# REGENIX_USB-C.net
KiCad netlist of a schematic drawn in Altium Designer
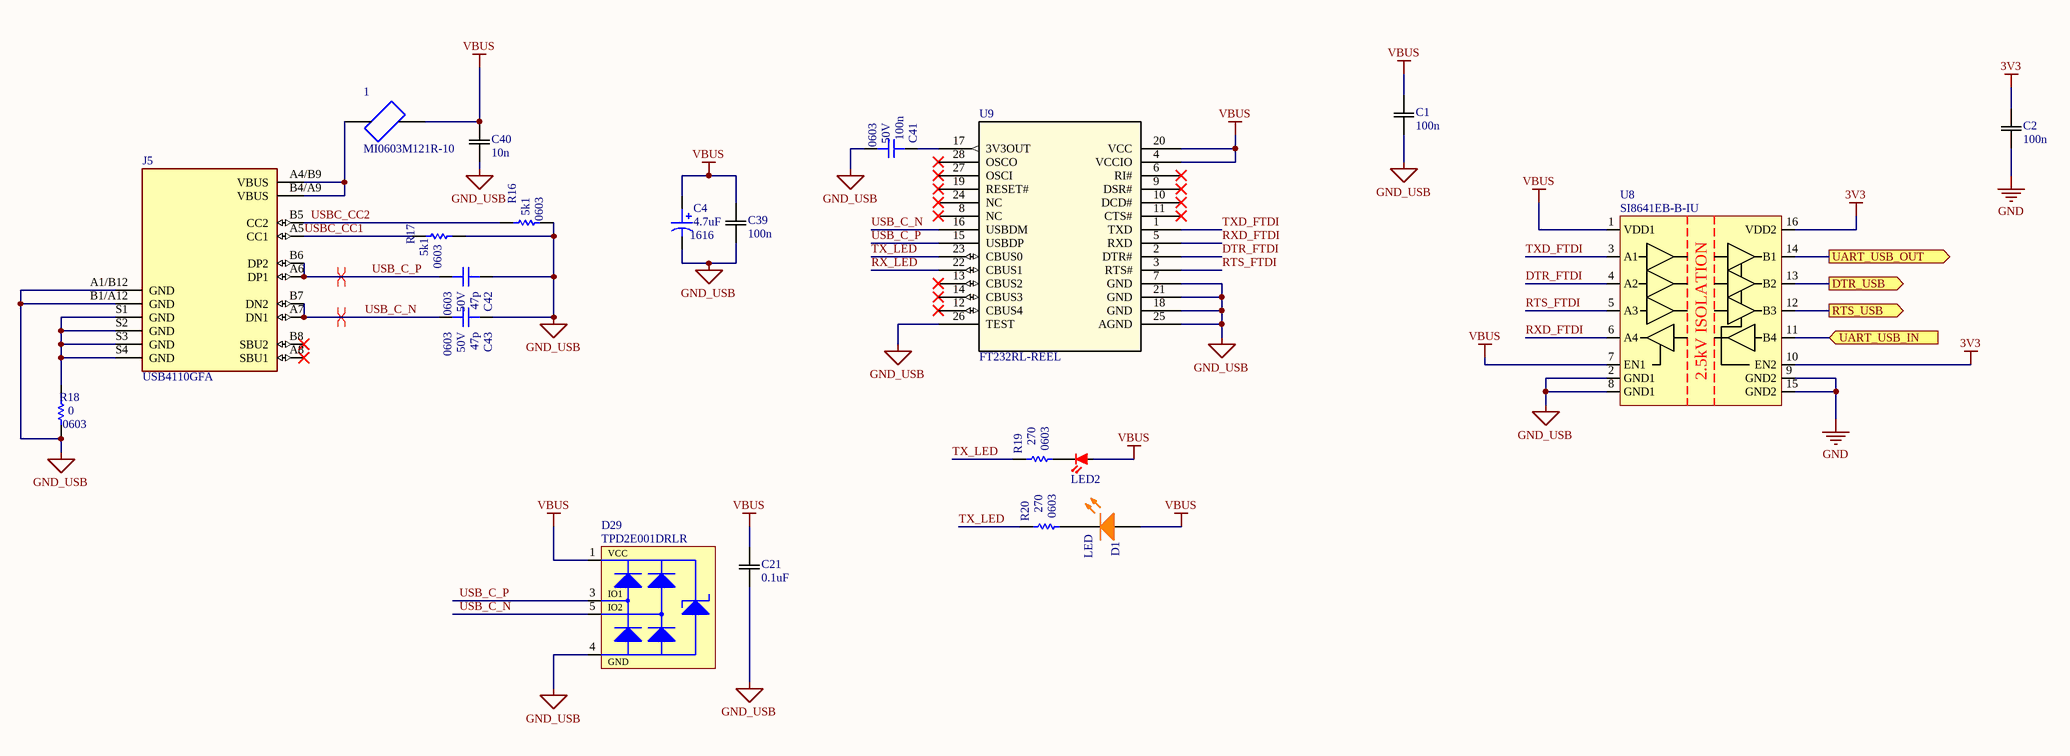
[diagram p0: REGENIX_USB-C.SchDoc]

(export (version "E")
  (design (tool "Eeschema 10.0.6"))
  (components
    (comp (ref "1")
      (value "MI0603M121R-10")
      (footprint "FB_MI0603M121R-10")
      (description "Ferrite Bead (Chip Bead), 1.6 x 0.8 x 0.8mm (0603), 120Ohms impedance at 25 MHz")
      (fields (field (name "MF") "Laird"))
      (libsource (lib "MI0603M121R-10") (part "MI0603M121R-10"))
    )
    (comp (ref "C1")
      (value "100n")
      (footprint "CAP_CL10_SAM")
      (description "CAP CER 0.1UF 50V X7R 0603 CL10B104KB8NNWC")
      (libsource (lib "CL10B104KB8NNWC") (part "CL10B104KB8NNWC"))
    )
    (comp (ref "C2")
      (value "100n")
      (footprint "CAP_CL10_SAM")
      (description "CAP CER 0.1UF 50V X7R 0603 CL10B104KB8NNWC")
      (libsource (lib "CL10B104KB8NNWC") (part "CL10B104KB8NNWC"))
    )
    (comp (ref "C4")
      (value "4.7uF")
      (footprint "CAP_ALU_1616_vishay")
      (description "CAP - ALU 470uF 20% 50V - 1616")
      (fields
        (field (name "MFG") "Vishay Dale")
        (field (name "MFG PART NUMBER") "MAL214699108E3")
        (field (name "PACKAGE") "1616")
        (field (name "CREATEDBY") "Jonathan Bouchard")
      )
      (libsource (lib "S7CAS_LIB2023") (part "CAP_ALU_MAL214699108E3"))
    )
    (comp (ref "C21")
      (value "0.1uF")
      (footprint "CAP_CL10_SAM")
      (description "CAP CER 0.1UF 50V X7R 0603 CL10B104KB8NNWC")
      (libsource (lib "CL10B104KB8NNWC") (part "CL10B104KB8NNWC"))
    )
    (comp (ref "C39")
      (value "100n")
      (footprint "CAP_CL10_SAM")
      (description "CAP CER 0.1UF 50V X7R 0603 CL10B104KB8NNWC")
      (libsource (lib "CL10B104KB8NNWC") (part "CL10B104KB8NNWC"))
    )
    (comp (ref "C40")
      (value "10n")
      (footprint "CAP_CL10_SAM")
      (description "CAP CER 0.1UF 50V X7R 0603 CL10B104KB8NNWC")
      (libsource (lib "CL10B104KB8NNWC") (part "CL10B104KB8NNWC"))
    )
    (comp (ref "C41")
      (value "100n")
      (footprint "CAP_0603")
      (description "CAP - 0603")
      (fields
        (field (name "VOLTAGE") "50V")
        (field (name "PACKAGE") "0603")
        (field (name "CREATEDBY") "Jonathan Bouchard")
      )
      (libsource (lib "S7CAS_LIB2023") (part "CAP - 0603"))
    )
    (comp (ref "C42")
      (value "47p")
      (footprint "CAP_0603")
      (description "CAP - 0603")
      (fields
        (field (name "VOLTAGE") "50V")
        (field (name "PACKAGE") "0603")
        (field (name "CREATEDBY") "Jonathan Bouchard")
      )
      (libsource (lib "S7CAS_LIB2023") (part "CAP - 0603"))
    )
    (comp (ref "C43")
      (value "47p")
      (footprint "CAP_0603")
      (description "CAP - 0603")
      (fields
        (field (name "VOLTAGE") "50V")
        (field (name "PACKAGE") "0603")
        (field (name "CREATEDBY") "Jonathan Bouchard")
      )
      (libsource (lib "S7CAS_LIB2023") (part "CAP - 0603"))
    )
    (comp (ref "D1")
      (value "LED")
      (footprint "LED_0603")
      (description "LED - 611nM ORANGE 2mA - 0603 SML-311DTT86")
      (fields
        (field (name "VOLTAGE") "1.8V")
        (field (name "MFG") "ROHM Semiconductor")
        (field (name "CREATEDBY") "Jonathan Bouchard")
      )
      (libsource (lib "S7CAS_LIB2023") (part "LED_SML-311DTT86"))
    )
    (comp (ref "D29")
      (value "TPD2E001DRLR")
      (footprint "TVS_USB_TPD2E001DRLR")
      (description "TVS - USB TVS DIODE 5.5V - SOT-553")
      (fields
        (field (name "CREATEDBY/DATE") "Jonathan Bouchard 2018-07-10")
        (field (name "VERIFIEDBY") "Arnaud Samson 16-07-18")
      )
      (libsource (lib "S7CAS_LIB2023") (part "TVS_USB_TPD2E001DRLR"))
    )
    (comp (ref "J5")
      (value "USB4110GFA")
      (footprint "GCT_USB4110GFA:GCT_USB4110GFA")
      (fields (field (name "MF") "Global Connector Technology"))
      (libsource (lib "USB4110GFA") (part "USB4110GFA"))
    )
    (comp (ref "LED2")
      (value "B1911USD-20D000114U1930")
      (footprint "LED-0603-2PIN")
      (description "LED RED CLEAR 1608 SMD")
      (libsource (lib "main_lib") (part "B1911USD-20D000114U1930"))
    )
    (comp (ref "R16")
      (value "5k1")
      (footprint "RES_0603")
      (description "RES - 0603")
      (fields (field (name "PACKAGE") "0603") (field (name "CREATEDBY") "Jonathan Bouchard"))
      (libsource (lib "S7CAS_LIB2023") (part "RES - 0603"))
    )
    (comp (ref "R17")
      (value "5k1")
      (footprint "RES_0603")
      (description "RES - 0603")
      (fields (field (name "PACKAGE") "0603") (field (name "CREATEDBY") "Jonathan Bouchard"))
      (libsource (lib "S7CAS_LIB2023") (part "RES - 0603"))
    )
    (comp (ref "R18")
      (value "0")
      (footprint "RES_0603")
      (description "RES - 0603")
      (fields (field (name "PACKAGE") "0603") (field (name "CREATEDBY") "Jonathan Bouchard"))
      (libsource (lib "S7CAS_LIB2023") (part "RES - 0603"))
    )
    (comp (ref "R19")
      (value "270")
      (footprint "RES_0603")
      (description "RES - 0603")
      (fields (field (name "PACKAGE") "0603") (field (name "CREATEDBY") "Jonathan Bouchard"))
      (libsource (lib "S7CAS_LIB2023") (part "RES - 0603"))
    )
    (comp (ref "R20")
      (value "270")
      (footprint "RES_0603")
      (description "RES - 0603")
      (fields (field (name "PACKAGE") "0603") (field (name "CREATEDBY") "Jonathan Bouchard"))
      (libsource (lib "S7CAS_LIB2023") (part "RES - 0603"))
    )
    (comp (ref "U8")
      (value "SI8641EB-B-IU")
      (footprint "ISO_SI8641EB-B-IU")
      (description "ISO - Quad-Channel Digital Isolator - 16-SSOP")
      (fields
        (field (name "CREATEDBY/DATE") "Louis-Daniel Gaulin / 25-02-2020")
        (field (name "VERIFIEDBY") "C.Paulin - 9/03/2020")
      )
      (libsource (lib "S7CAS_LIB2023") (part "ISO_SI8641EB-B-IU"))
    )
    (comp (ref "U9")
      (value "FT232RL-REEL")
      (footprint "IC28_SSOP-28_FTD")
      (description "No Description Available")
      (libsource (lib "FT232RL-REEL") (part "FT232RL-REEL"))
    )
  )
  (nets
    (net (code "1") (name "/DTR_FTDI") (class "Default")
      (node (ref "U8") (pin "4") (pinfunction "A2_4") (pintype "passive"))
      (node (ref "U9") (pin "2") (pinfunction "DTR#_2") (pintype "passive"))
    )
    (net (code "2") (name "/DTR_USB") (class "Default")
      (node (ref "U8") (pin "13") (pinfunction "B2_13") (pintype "passive"))
    )
    (net (code "3") (name "/RTS_FTDI") (class "Default")
      (node (ref "U8") (pin "5") (pinfunction "A3_5") (pintype "passive"))
      (node (ref "U9") (pin "3") (pinfunction "RTS#_3") (pintype "passive"))
    )
    (net (code "4") (name "/RTS_USB") (class "Default")
      (node (ref "U8") (pin "12") (pinfunction "B3_12") (pintype "passive"))
    )
    (net (code "5") (name "/RXD_FTDI") (class "Default")
      (node (ref "U8") (pin "6") (pinfunction "A4_6") (pintype "passive"))
      (node (ref "U9") (pin "5") (pinfunction "RXD_5") (pintype "passive"))
    )
    (net (code "6") (name "/RX_LED") (class "Default")
      (node (ref "U9") (pin "22") (pinfunction "CBUS1_22") (pintype "bidirectional"))
    )
    (net (code "7") (name "/TXD_FTDI") (class "Default")
      (node (ref "U8") (pin "3") (pinfunction "A1_3") (pintype "passive"))
      (node (ref "U9") (pin "1") (pinfunction "TXD_1") (pintype "passive"))
    )
    (net (code "8") (name "/TX_LED") (class "Default")
      (node (ref "R19") (pin "2") (pinfunction "2_2") (pintype "passive"))
      (node (ref "R20") (pin "2") (pinfunction "2_2") (pintype "passive"))
      (node (ref "U9") (pin "23") (pinfunction "CBUS0_23") (pintype "bidirectional"))
    )
    (net (code "9") (name "/UART_USB_IN") (class "Default")
      (node (ref "U8") (pin "11") (pinfunction "B4_11") (pintype "passive"))
    )
    (net (code "10") (name "/UART_USB_OUT") (class "Default")
      (node (ref "U8") (pin "14") (pinfunction "B1_14") (pintype "passive"))
    )
    (net (code "11") (name "/USBC_CC1") (class "Default")
      (node (ref "J5") (pin "A5") (pinfunction "CC1_A5") (pintype "bidirectional"))
      (node (ref "R17") (pin "2") (pinfunction "2_2") (pintype "passive"))
    )
    (net (code "12") (name "/USBC_CC2") (class "Default")
      (node (ref "J5") (pin "B5") (pinfunction "CC2_B5") (pintype "bidirectional"))
      (node (ref "R16") (pin "2") (pinfunction "2_2") (pintype "passive"))
    )
    (net (code "13") (name "/USB_C_N") (class "Default")
      (node (ref "C43") (pin "1") (pinfunction "1_1") (pintype "passive"))
      (node (ref "D29") (pin "5") (pinfunction "IO2_5") (pintype "passive"))
      (node (ref "J5") (pin "A7") (pinfunction "DN1_A7") (pintype "bidirectional"))
      (node (ref "J5") (pin "B7") (pinfunction "DN2_B7") (pintype "bidirectional"))
      (node (ref "U9") (pin "16") (pinfunction "USBDM_16") (pintype "passive"))
    )
    (net (code "14") (name "/USB_C_P") (class "Default")
      (node (ref "C42") (pin "1") (pinfunction "1_1") (pintype "passive"))
      (node (ref "D29") (pin "3") (pinfunction "IO1_3") (pintype "passive"))
      (node (ref "J5") (pin "A6") (pinfunction "DP1_A6") (pintype "bidirectional"))
      (node (ref "J5") (pin "B6") (pinfunction "DP2_B6") (pintype "bidirectional"))
      (node (ref "U9") (pin "15") (pinfunction "USBDP_15") (pintype "passive"))
    )
    (net (code "15") (name "3V3") (class "Default")
      (node (ref "C2") (pin "2") (pinfunction "2_2") (pintype "passive"))
      (node (ref "U8") (pin "10") (pinfunction "EN2_10") (pintype "passive"))
      (node (ref "U8") (pin "16") (pinfunction "VDD2_16") (pintype "passive"))
    )
    (net (code "16") (name "GND") (class "Default")
      (node (ref "C2") (pin "1") (pinfunction "1_1") (pintype "passive"))
      (node (ref "U8") (pin "15") (pinfunction "GND2_15") (pintype "passive"))
      (node (ref "U8") (pin "9") (pinfunction "GND2_9") (pintype "passive"))
    )
    (net (code "17") (name "GND_USB") (class "Default")
      (node (ref "C1") (pin "1") (pinfunction "1_1") (pintype "passive"))
      (node (ref "C21") (pin "1") (pinfunction "1_1") (pintype "passive"))
      (node (ref "C39") (pin "1") (pinfunction "1_1") (pintype "passive"))
      (node (ref "C4") (pin "2") (pinfunction "2_2") (pintype "passive"))
      (node (ref "C40") (pin "1") (pinfunction "1_1") (pintype "passive"))
      (node (ref "C41") (pin "1") (pinfunction "1_1") (pintype "passive"))
      (node (ref "C42") (pin "2") (pinfunction "2_2") (pintype "passive"))
      (node (ref "C43") (pin "2") (pinfunction "2_2") (pintype "passive"))
      (node (ref "D29") (pin "4") (pinfunction "GND_4") (pintype "passive"))
      (node (ref "J5") (pin "A1/B12") (pinfunction "GND_A1/B12") (pintype "power_in"))
      (node (ref "J5") (pin "B1/A12") (pinfunction "GND_B1/A12") (pintype "power_in"))
      (node (ref "R16") (pin "1") (pinfunction "1_1") (pintype "passive"))
      (node (ref "R17") (pin "1") (pinfunction "1_1") (pintype "passive"))
      (node (ref "R18") (pin "1") (pinfunction "1_1") (pintype "passive"))
      (node (ref "U8") (pin "2") (pinfunction "GND1_2") (pintype "passive"))
      (node (ref "U8") (pin "8") (pinfunction "GND1_8") (pintype "passive"))
      (node (ref "U9") (pin "18") (pinfunction "GND_18") (pintype "power_in"))
      (node (ref "U9") (pin "21") (pinfunction "GND_21") (pintype "power_in"))
      (node (ref "U9") (pin "25") (pinfunction "AGND_25") (pintype "power_in"))
      (node (ref "U9") (pin "26") (pinfunction "TEST_26") (pintype "passive"))
      (node (ref "U9") (pin "7") (pinfunction "GND_7") (pintype "power_in"))
    )
    (net (code "18") (name "Net-(1-Pad1)") (class "Default")
      (node (ref "1") (pin "1") (pinfunction "1_1") (pintype "passive"))
      (node (ref "J5") (pin "A4/B9") (pinfunction "VBUS_A4/B9") (pintype "power_in"))
      (node (ref "J5") (pin "B4/A9") (pinfunction "VBUS_B4/A9") (pintype "power_in"))
    )
    (net (code "19") (name "Net-(D1-PadK)") (class "Default")
      (node (ref "D1") (pin "K") (pinfunction "K_K") (pintype "passive"))
      (node (ref "R20") (pin "1") (pinfunction "1_1") (pintype "passive"))
    )
    (net (code "20") (name "Net-(J5-GND-PadS1)") (class "Default")
      (node (ref "J5") (pin "S1") (pinfunction "GND_S1") (pintype "power_in"))
      (node (ref "J5") (pin "S2") (pinfunction "GND_S2") (pintype "power_in"))
      (node (ref "J5") (pin "S3") (pinfunction "GND_S3") (pintype "power_in"))
      (node (ref "J5") (pin "S4") (pinfunction "GND_S4") (pintype "power_in"))
      (node (ref "R18") (pin "2") (pinfunction "2_2") (pintype "passive"))
    )
    (net (code "21") (name "Net-(LED2-K)") (class "Default")
      (node (ref "LED2") (pin "1") (pinfunction "K_1") (pintype "passive"))
      (node (ref "R19") (pin "1") (pinfunction "1_1") (pintype "passive"))
    )
    (net (code "22") (name "Net-(U9-3V3OUT)") (class "Default")
      (node (ref "C41") (pin "2") (pinfunction "2_2") (pintype "passive"))
      (node (ref "U9") (pin "17") (pinfunction "3V3OUT_17") (pintype "output"))
    )
    (net (code "23") (name "VBUS") (class "Default")
      (node (ref "1") (pin "2") (pinfunction "2_2") (pintype "passive"))
      (node (ref "C1") (pin "2") (pinfunction "2_2") (pintype "passive"))
      (node (ref "C21") (pin "2") (pinfunction "2_2") (pintype "passive"))
      (node (ref "C39") (pin "2") (pinfunction "2_2") (pintype "passive"))
      (node (ref "C4") (pin "1") (pinfunction "1_1") (pintype "passive"))
      (node (ref "C40") (pin "2") (pinfunction "2_2") (pintype "passive"))
      (node (ref "D1") (pin "A") (pinfunction "A_A") (pintype "passive"))
      (node (ref "D29") (pin "1") (pinfunction "VCC_1") (pintype "passive"))
      (node (ref "LED2") (pin "2") (pinfunction "R_2") (pintype "passive"))
      (node (ref "U8") (pin "1") (pinfunction "VDD1_1") (pintype "passive"))
      (node (ref "U8") (pin "7") (pinfunction "EN1_7") (pintype "passive"))
      (node (ref "U9") (pin "20") (pinfunction "VCC_20") (pintype "power_in"))
      (node (ref "U9") (pin "4") (pinfunction "VCCIO_4") (pintype "power_in"))
    )
    (net (code "24") (name "unconnected-(D29-NC-Pad2)") (class "Default")
      (node (ref "D29") (pin "2") (pinfunction "NC_2") (pintype "passive"))
    )
    (net (code "25") (name "unconnected-(J5-SBU1-PadA8)") (class "Default")
      (node (ref "J5") (pin "A8") (pinfunction "SBU1_A8") (pintype "bidirectional+no_connect"))
    )
    (net (code "26") (name "unconnected-(J5-SBU2-PadB8)") (class "Default")
      (node (ref "J5") (pin "B8") (pinfunction "SBU2_B8") (pintype "bidirectional+no_connect"))
    )
    (net (code "27") (name "unconnected-(U9-CBUS2-Pad13)") (class "Default")
      (node (ref "U9") (pin "13") (pinfunction "CBUS2_13") (pintype "bidirectional+no_connect"))
    )
    (net (code "28") (name "unconnected-(U9-CBUS3-Pad14)") (class "Default")
      (node (ref "U9") (pin "14") (pinfunction "CBUS3_14") (pintype "bidirectional+no_connect"))
    )
    (net (code "29") (name "unconnected-(U9-CBUS4-Pad12)") (class "Default")
      (node (ref "U9") (pin "12") (pinfunction "CBUS4_12") (pintype "bidirectional+no_connect"))
    )
    (net (code "30") (name "unconnected-(U9-CTS#-Pad11)") (class "Default")
      (node (ref "U9") (pin "11") (pinfunction "CTS#_11") (pintype "passive+no_connect"))
    )
    (net (code "31") (name "unconnected-(U9-DCD#-Pad10)") (class "Default")
      (node (ref "U9") (pin "10") (pinfunction "DCD#_10") (pintype "passive+no_connect"))
    )
    (net (code "32") (name "unconnected-(U9-DSR#-Pad9)") (class "Default")
      (node (ref "U9") (pin "9") (pinfunction "DSR#_9") (pintype "passive+no_connect"))
    )
    (net (code "33") (name "unconnected-(U9-NC-Pad8)") (class "Default")
      (node (ref "U9") (pin "8") (pinfunction "NC_8") (pintype "passive+no_connect"))
    )
    (net (code "34") (name "unconnected-(U9-NC-Pad24)") (class "Default")
      (node (ref "U9") (pin "24") (pinfunction "NC_24") (pintype "passive+no_connect"))
    )
    (net (code "35") (name "unconnected-(U9-OSCI-Pad27)") (class "Default")
      (node (ref "U9") (pin "27") (pinfunction "OSCI_27") (pintype "passive+no_connect"))
    )
    (net (code "36") (name "unconnected-(U9-OSCO-Pad28)") (class "Default")
      (node (ref "U9") (pin "28") (pinfunction "OSCO_28") (pintype "passive+no_connect"))
    )
    (net (code "37") (name "unconnected-(U9-RESET#-Pad19)") (class "Default")
      (node (ref "U9") (pin "19") (pinfunction "RESET#_19") (pintype "passive+no_connect"))
    )
    (net (code "38") (name "unconnected-(U9-RI#-Pad6)") (class "Default")
      (node (ref "U9") (pin "6") (pinfunction "RI#_6") (pintype "passive+no_connect"))
    )
  )
)
